# MP-USBC.net
KiCad netlist of a schematic drawn in Altium Designer
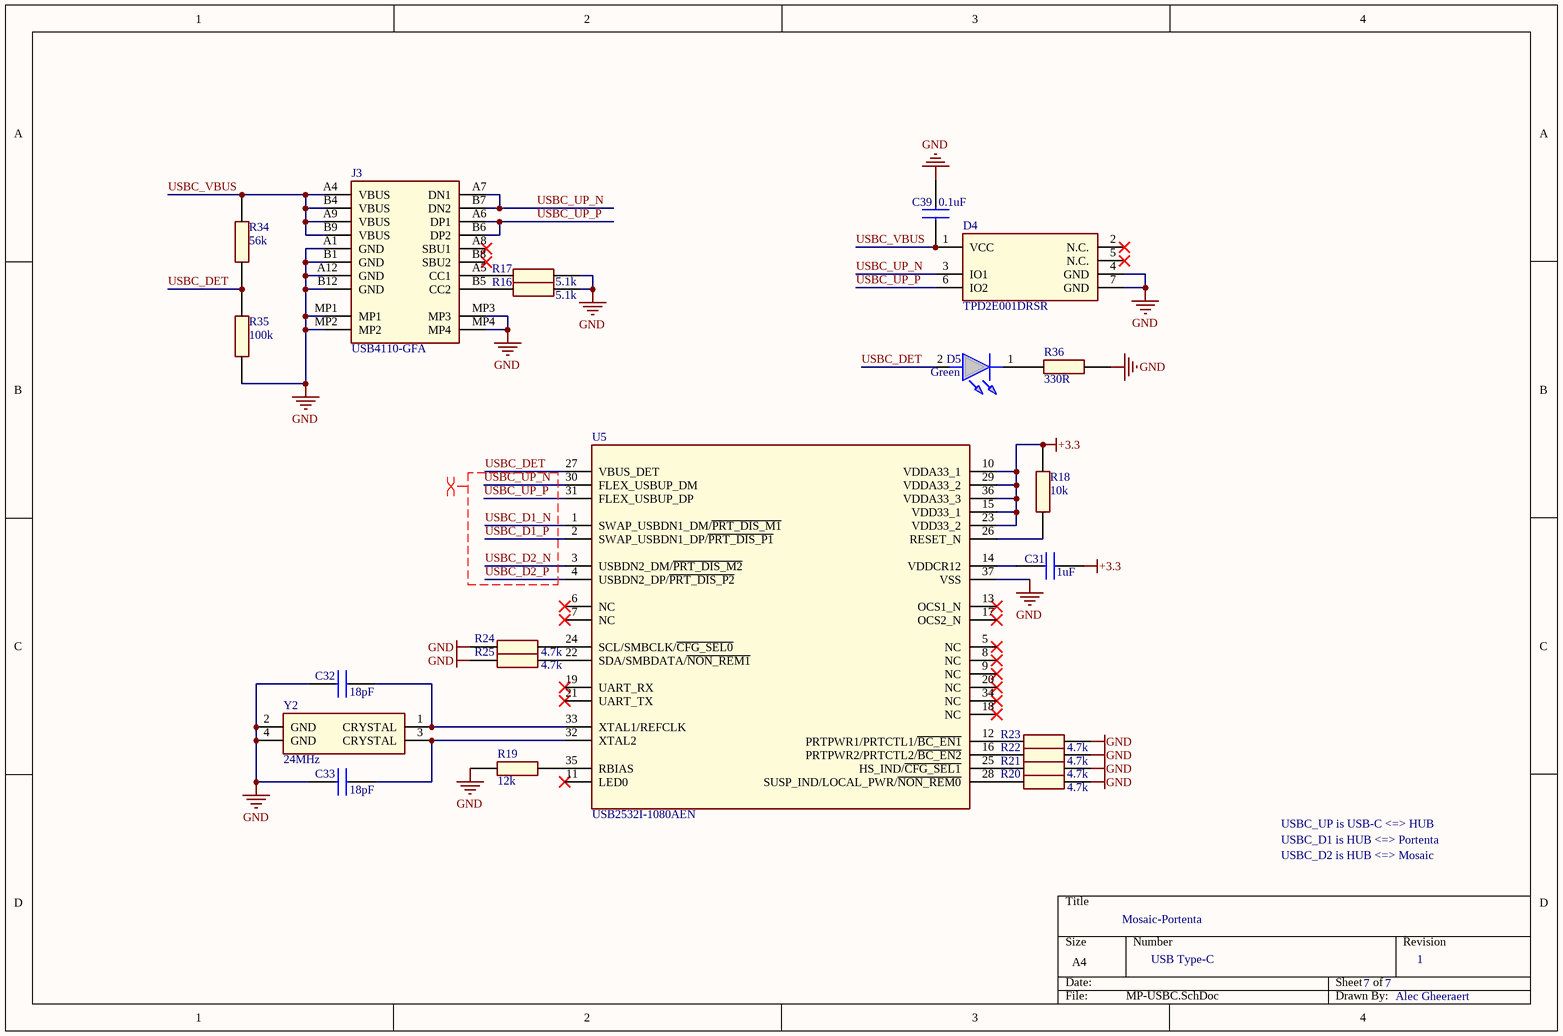
[diagram p0: MP-USBC.SchDoc]

(export (version "E")
  (design (tool "Eeschema 10.0.6"))
  (components
    (comp (ref "C31")
      (value "1uF")
      (footprint "CAPC1608X100N")
      (description "0603 1µF")
      (fields (field (name "MANUFACTURER") "Walsin") (field (name "TOLERANCE") "10%"))
      (libsource (lib "Ghrt") (part "0603X105K6R3CT"))
    )
    (comp (ref "C32")
      (value "18pF")
      (footprint "CAPC1608X87N")
      (description "0603 18pF")
      (fields (field (name "TOLERANCE") "5%") (field (name "MANUFACTURER") "Walsin"))
      (libsource (lib "Ghrt") (part "0603N180J160CT"))
    )
    (comp (ref "C33")
      (value "18pF")
      (footprint "CAPC1608X87N")
      (description "0603 18pF")
      (fields (field (name "TOLERANCE") "5%") (field (name "MANUFACTURER") "Walsin"))
      (libsource (lib "Ghrt") (part "0603N180J160CT"))
    )
    (comp (ref "C39")
      (value "0.1uF")
      (footprint "CAPC2012X145N")
      (description "0805I 0.1µF")
      (fields (field (name "MANUFACTURER") "Walsin") (field (name "TOLERANCE") "10%"))
      (libsource (lib "Ghrt") (part "MG21B104K101CT"))
    )
    (comp (ref "D4")
      (value "TPD2E001DRSR")
      (footprint "SON95P300X300X80-7N-D")
      (description "2-Channel TVS Diode")
      (libsource (lib "Ghrt") (part "TPD2E001DRSR"))
    )
    (comp (ref "D5")
      (value "Green")
      (footprint "APT1608ZGCAMT")
      (description "0603 Green LED")
      (libsource (lib "Ghrt") (part "APT1608ZGC-AMT"))
    )
    (comp (ref "J3")
      (value "USB4110-GFA")
      (footprint "USB4110-GFA")
      (description "USB-2.0 Type C")
      (fields (field (name "MANUFACTURER") "Global Connector Technologies"))
      (libsource (lib "Ghrt") (part "USB4110-GFA"))
    )
    (comp (ref "R16")
      (value "5.1k")
      (footprint "RESC1608X60N")
      (description "0603I 5.1k")
      (fields (field (name "MANUFACTURER") "Walsin") (field (name "TOLERANCE") "1%"))
      (libsource (lib "Ghrt") (part "WR06X5101FTL"))
    )
    (comp (ref "R17")
      (value "5.1k")
      (footprint "RESC1608X60N")
      (description "0603I 5.1k")
      (fields (field (name "MANUFACTURER") "Walsin") (field (name "TOLERANCE") "1%"))
      (libsource (lib "Ghrt") (part "WR06X5101FTL"))
    )
    (comp (ref "R18")
      (value "10k")
      (footprint "RESC1005X40N")
      (description "0402I 10k")
      (fields (field (name "MANUFACTURER") "Walsin") (field (name "TOLERANCE") "1%"))
      (libsource (lib "Ghrt") (part "WR04X1002FTL"))
    )
    (comp (ref "R19")
      (value "12k")
      (footprint "RESC1005X40N")
      (description "0402I 12k")
      (fields (field (name "TOLERANCE") "1%") (field (name "MANUFACTURER") "Walsin"))
      (libsource (lib "Ghrt") (part "WR04X1202FTL"))
    )
    (comp (ref "R20")
      (value "4.7k")
      (footprint "RESC1005X40N")
      (description "0402I 4.7k")
      (fields (field (name "MANUFACTURER") "Walsin") (field (name "TOLERANCE") "1%"))
      (libsource (lib "Ghrt") (part "WR04X4701FTL"))
    )
    (comp (ref "R21")
      (value "4.7k")
      (footprint "RESC1005X40N")
      (description "0402I 4.7k")
      (fields (field (name "MANUFACTURER") "Walsin") (field (name "TOLERANCE") "1%"))
      (libsource (lib "Ghrt") (part "WR04X4701FTL"))
    )
    (comp (ref "R22")
      (value "4.7k")
      (footprint "RESC1005X40N")
      (description "0402I 4.7k")
      (fields (field (name "MANUFACTURER") "Walsin") (field (name "TOLERANCE") "1%"))
      (libsource (lib "Ghrt") (part "WR04X4701FTL"))
    )
    (comp (ref "R23")
      (value "4.7k")
      (footprint "RESC1005X40N")
      (description "0402I 4.7k")
      (fields (field (name "MANUFACTURER") "Walsin") (field (name "TOLERANCE") "1%"))
      (libsource (lib "Ghrt") (part "WR04X4701FTL"))
    )
    (comp (ref "R24")
      (value "4.7k")
      (footprint "RESC1005X40N")
      (description "0402I 4.7k")
      (fields (field (name "MANUFACTURER") "Walsin") (field (name "TOLERANCE") "1%"))
      (libsource (lib "Ghrt") (part "WR04X4701FTL"))
    )
    (comp (ref "R25")
      (value "4.7k")
      (footprint "RESC1005X40N")
      (description "0402I 4.7k")
      (fields (field (name "MANUFACTURER") "Walsin") (field (name "TOLERANCE") "1%"))
      (libsource (lib "Ghrt") (part "WR04X4701FTL"))
    )
    (comp (ref "R34")
      (value "56k")
      (footprint "RESC1005X40N")
      (description "0402I 56k")
      (fields (field (name "TOLERANCE") "1%") (field (name "MANUFACTURER") "Walsin"))
      (libsource (lib "Ghrt") (part "WR04X5602FTL"))
    )
    (comp (ref "R35")
      (value "100k")
      (footprint "RESC1005X40N")
      (description "0402I 100k")
      (fields (field (name "MANUFACTURER") "Walsin") (field (name "TOLERANCE") "1%"))
      (libsource (lib "Ghrt") (part "WR04X1003FTL"))
    )
    (comp (ref "R36")
      (value "330R")
      (footprint "RESC1005X40N")
      (description "0402I 330")
      (fields (field (name "TOLERANCE") "1%") (field (name "MANUFACTURER") "Walsin"))
      (libsource (lib "Ghrt") (part "WR04X3300FTL"))
    )
    (comp (ref "U5")
      (value "USB2532I-1080AEN")
      (footprint "QFN50P600X600X100-37N-D")
      (description "2-Port USB-2.0 Controller Hub")
      (fields (field (name "MANUFACTURER") "Microchip"))
      (libsource (lib "Ghrt") (part "USB2532I-1080AEN"))
    )
    (comp (ref "Y2")
      (value "24MHz")
      (footprint "LFXTAL071257Reel")
      (description "24MHz +/-100ppm Crystal")
      (fields (field (name "TOLERANCE") "10") (field (name "MANUFACTURER") "IQD"))
      (libsource (lib "Ghrt") (part "LFXTAL071257Reel"))
    )
  )
  (nets
    (net (code "1") (name "+3.3") (class "Default")
      (node (ref "C31") (pin "2") (pinfunction "2_2") (pintype "passive"))
      (node (ref "R18") (pin "2") (pinfunction "2_2") (pintype "passive"))
      (node (ref "U5") (pin "10") (pinfunction "VDDA33_1_10") (pintype "passive"))
      (node (ref "U5") (pin "15") (pinfunction "VDD33_1_15") (pintype "passive"))
      (node (ref "U5") (pin "23") (pinfunction "VDD33_2_23") (pintype "passive"))
      (node (ref "U5") (pin "29") (pinfunction "VDDA33_2_29") (pintype "passive"))
      (node (ref "U5") (pin "36") (pinfunction "VDDA33_3_36") (pintype "passive"))
    )
    (net (code "3") (name "/USBC_D1_N") (class "Default")
      (node (ref "U5") (pin "1") (pinfunction "SWAP_USBDN1_DM/~{PRT_DIS_M1}_1") (pintype "passive"))
    )
    (net (code "4") (name "/USBC_D1_P") (class "Default")
      (node (ref "U5") (pin "2") (pinfunction "SWAP_USBDN1_DP/~{PRT_DIS_P1}_2") (pintype "passive"))
    )
    (net (code "5") (name "/USBC_D2_N") (class "Default")
      (node (ref "U5") (pin "3") (pinfunction "USBDN2_DM/~{PRT_DIS_M2}_3") (pintype "passive"))
    )
    (net (code "6") (name "/USBC_D2_P") (class "Default")
      (node (ref "U5") (pin "4") (pinfunction "USBDN2_DP/~{PRT_DIS_P2}_4") (pintype "passive"))
    )
    (net (code "7") (name "/USBC_DET") (class "Default")
      (node (ref "D5") (pin "2") (pinfunction "A_2") (pintype "passive"))
      (node (ref "R34") (pin "2") (pinfunction "2_2") (pintype "passive"))
      (node (ref "R35") (pin "1") (pinfunction "1_1") (pintype "passive"))
      (node (ref "U5") (pin "27") (pinfunction "VBUS_DET_27") (pintype "passive"))
    )
    (net (code "8") (name "/USBC_UP_N") (class "Default")
      (node (ref "D4") (pin "3") (pinfunction "IO1_3") (pintype "passive"))
      (node (ref "J3") (pin "A7") (pinfunction "DN1_A7") (pintype "passive"))
      (node (ref "J3") (pin "B7") (pinfunction "DN2_B7") (pintype "passive"))
      (node (ref "U5") (pin "30") (pinfunction "FLEX_USBUP_DM_30") (pintype "passive"))
    )
    (net (code "9") (name "/USBC_UP_P") (class "Default")
      (node (ref "D4") (pin "6") (pinfunction "IO2_6") (pintype "passive"))
      (node (ref "J3") (pin "A6") (pinfunction "DP1_A6") (pintype "passive"))
      (node (ref "J3") (pin "B6") (pinfunction "DP2_B6") (pintype "passive"))
      (node (ref "U5") (pin "31") (pinfunction "FLEX_USBUP_DP_31") (pintype "passive"))
    )
    (net (code "10") (name "/USBC_VBUS") (class "Default")
      (node (ref "C39") (pin "1") (pinfunction "1_1") (pintype "passive"))
      (node (ref "D4") (pin "1") (pinfunction "VCC_1") (pintype "passive"))
      (node (ref "J3") (pin "A4") (pinfunction "VBUS_A4") (pintype "passive"))
      (node (ref "J3") (pin "A9") (pinfunction "VBUS_A9") (pintype "passive"))
      (node (ref "J3") (pin "B4") (pinfunction "VBUS_B4") (pintype "passive"))
      (node (ref "J3") (pin "B9") (pinfunction "VBUS_B9") (pintype "passive"))
      (node (ref "R34") (pin "1") (pinfunction "1_1") (pintype "passive"))
    )
    (net (code "11") (name "GND") (class "Default")
      (node (ref "C32") (pin "1") (pinfunction "1_1") (pintype "passive"))
      (node (ref "C33") (pin "1") (pinfunction "1_1") (pintype "passive"))
      (node (ref "C39") (pin "2") (pinfunction "2_2") (pintype "passive"))
      (node (ref "D4") (pin "4") (pinfunction "GND_4") (pintype "passive"))
      (node (ref "D4") (pin "7") (pinfunction "GND_7") (pintype "passive"))
      (node (ref "J3") (pin "A1") (pinfunction "GND_A1") (pintype "passive"))
      (node (ref "J3") (pin "A12") (pinfunction "GND_A12") (pintype "passive"))
      (node (ref "J3") (pin "B1") (pinfunction "GND_B1") (pintype "passive"))
      (node (ref "J3") (pin "B12") (pinfunction "GND_B12") (pintype "passive"))
      (node (ref "J3") (pin "MP1") (pinfunction "MP1_MP1") (pintype "passive"))
      (node (ref "J3") (pin "MP2") (pinfunction "MP2_MP2") (pintype "passive"))
      (node (ref "J3") (pin "MP3") (pinfunction "MP3_MP3") (pintype "passive"))
      (node (ref "J3") (pin "MP4") (pinfunction "MP4_MP4") (pintype "passive"))
      (node (ref "R16") (pin "2") (pinfunction "2_2") (pintype "passive"))
      (node (ref "R17") (pin "2") (pinfunction "2_2") (pintype "passive"))
      (node (ref "R19") (pin "2") (pinfunction "2_2") (pintype "passive"))
      (node (ref "R20") (pin "2") (pinfunction "2_2") (pintype "passive"))
      (node (ref "R21") (pin "2") (pinfunction "2_2") (pintype "passive"))
      (node (ref "R22") (pin "2") (pinfunction "2_2") (pintype "passive"))
      (node (ref "R23") (pin "2") (pinfunction "2_2") (pintype "passive"))
      (node (ref "R24") (pin "1") (pinfunction "1_1") (pintype "passive"))
      (node (ref "R25") (pin "1") (pinfunction "1_1") (pintype "passive"))
      (node (ref "R35") (pin "2") (pinfunction "2_2") (pintype "passive"))
      (node (ref "R36") (pin "2") (pinfunction "2_2") (pintype "passive"))
      (node (ref "U5") (pin "37") (pinfunction "VSS_37") (pintype "passive"))
      (node (ref "Y2") (pin "2") (pinfunction "GND_2") (pintype "passive"))
      (node (ref "Y2") (pin "4") (pinfunction "GND_4") (pintype "passive"))
    )
    (net (code "12") (name "Net-(D5-K)") (class "Default")
      (node (ref "D5") (pin "1") (pinfunction "K_1") (pintype "passive"))
      (node (ref "R36") (pin "1") (pinfunction "1_1") (pintype "passive"))
    )
    (net (code "13") (name "Net-(J3-CC1)") (class "Default")
      (node (ref "J3") (pin "A5") (pinfunction "CC1_A5") (pintype "passive"))
      (node (ref "R17") (pin "1") (pinfunction "1_1") (pintype "passive"))
    )
    (net (code "14") (name "Net-(J3-CC2)") (class "Default")
      (node (ref "J3") (pin "B5") (pinfunction "CC2_B5") (pintype "passive"))
      (node (ref "R16") (pin "1") (pinfunction "1_1") (pintype "passive"))
    )
    (net (code "15") (name "Net-(U5-HS_IND{slash}~{CFG_SEL1})") (class "Default")
      (node (ref "R21") (pin "1") (pinfunction "1_1") (pintype "passive"))
      (node (ref "U5") (pin "25") (pinfunction "HS_IND/~{CFG_SEL1}_25") (pintype "passive"))
    )
    (net (code "16") (name "Net-(U5-PRTPWR1{slash}PRTCTL1{slash}~{BC_EN1})") (class "Default")
      (node (ref "R23") (pin "1") (pinfunction "1_1") (pintype "passive"))
      (node (ref "U5") (pin "12") (pinfunction "PRTPWR1/PRTCTL1/~{BC_EN1}_12") (pintype "passive"))
    )
    (net (code "17") (name "Net-(U5-PRTPWR2{slash}PRTCTL2{slash}~{BC_EN2})") (class "Default")
      (node (ref "R22") (pin "1") (pinfunction "1_1") (pintype "passive"))
      (node (ref "U5") (pin "16") (pinfunction "PRTPWR2/PRTCTL2/~{BC_EN2}_16") (pintype "passive"))
    )
    (net (code "18") (name "Net-(U5-RBIAS)") (class "Default")
      (node (ref "R19") (pin "1") (pinfunction "1_1") (pintype "passive"))
      (node (ref "U5") (pin "35") (pinfunction "RBIAS_35") (pintype "passive"))
    )
    (net (code "19") (name "Net-(U5-RESET_N)") (class "Default")
      (node (ref "R18") (pin "1") (pinfunction "1_1") (pintype "passive"))
      (node (ref "U5") (pin "26") (pinfunction "RESET_N_26") (pintype "passive"))
    )
    (net (code "20") (name "Net-(U5-SCL{slash}SMBCLK{slash}~{CFG_SEL0})") (class "Default")
      (node (ref "R24") (pin "2") (pinfunction "2_2") (pintype "passive"))
      (node (ref "U5") (pin "24") (pinfunction "SCL/SMBCLK/~{CFG_SEL0}_24") (pintype "passive"))
    )
    (net (code "21") (name "Net-(U5-SDA{slash}SMBDATA{slash}~{NON_REM1})") (class "Default")
      (node (ref "R25") (pin "2") (pinfunction "2_2") (pintype "passive"))
      (node (ref "U5") (pin "22") (pinfunction "SDA/SMBDATA/~{NON_REM1}_22") (pintype "passive"))
    )
    (net (code "22") (name "Net-(U5-SUSP_IND{slash}LOCAL_PWR{slash}~{NON_REM0})") (class "Default")
      (node (ref "R20") (pin "1") (pinfunction "1_1") (pintype "passive"))
      (node (ref "U5") (pin "28") (pinfunction "SUSP_IND/LOCAL_PWR/~{NON_REM0}_28") (pintype "passive"))
    )
    (net (code "23") (name "Net-(U5-VDDCR12)") (class "Default")
      (node (ref "C31") (pin "1") (pinfunction "1_1") (pintype "passive"))
      (node (ref "U5") (pin "14") (pinfunction "VDDCR12_14") (pintype "passive"))
    )
    (net (code "24") (name "Net-(U5-XTAL1{slash}REFCLK)") (class "Default")
      (node (ref "C32") (pin "2") (pinfunction "2_2") (pintype "passive"))
      (node (ref "U5") (pin "33") (pinfunction "XTAL1/REFCLK_33") (pintype "passive"))
      (node (ref "Y2") (pin "1") (pinfunction "CRYSTAL_1") (pintype "passive"))
    )
    (net (code "25") (name "Net-(U5-XTAL2)") (class "Default")
      (node (ref "C33") (pin "2") (pinfunction "2_2") (pintype "passive"))
      (node (ref "U5") (pin "32") (pinfunction "XTAL2_32") (pintype "passive"))
      (node (ref "Y2") (pin "3") (pinfunction "CRYSTAL_3") (pintype "passive"))
    )
    (net (code "26") (name "unconnected-(D4-N.C.-Pad2)") (class "Default")
      (node (ref "D4") (pin "2") (pinfunction "N.C._2") (pintype "passive+no_connect"))
    )
    (net (code "27") (name "unconnected-(D4-N.C.-Pad5)") (class "Default")
      (node (ref "D4") (pin "5") (pinfunction "N.C._5") (pintype "passive+no_connect"))
    )
    (net (code "28") (name "unconnected-(J3-SBU1-PadA8)") (class "Default")
      (node (ref "J3") (pin "A8") (pinfunction "SBU1_A8") (pintype "passive+no_connect"))
    )
    (net (code "29") (name "unconnected-(J3-SBU2-PadB8)") (class "Default")
      (node (ref "J3") (pin "B8") (pinfunction "SBU2_B8") (pintype "passive+no_connect"))
    )
    (net (code "30") (name "unconnected-(U5-LED0-Pad11)") (class "Default")
      (node (ref "U5") (pin "11") (pinfunction "LED0_11") (pintype "passive+no_connect"))
    )
    (net (code "31") (name "unconnected-(U5-NC-Pad5)") (class "Default")
      (node (ref "U5") (pin "5") (pinfunction "NC_5") (pintype "passive+no_connect"))
    )
    (net (code "32") (name "unconnected-(U5-NC-Pad6)") (class "Default")
      (node (ref "U5") (pin "6") (pinfunction "NC_6") (pintype "passive+no_connect"))
    )
    (net (code "33") (name "unconnected-(U5-NC-Pad7)") (class "Default")
      (node (ref "U5") (pin "7") (pinfunction "NC_7") (pintype "passive+no_connect"))
    )
    (net (code "34") (name "unconnected-(U5-NC-Pad8)") (class "Default")
      (node (ref "U5") (pin "8") (pinfunction "NC_8") (pintype "passive+no_connect"))
    )
    (net (code "35") (name "unconnected-(U5-NC-Pad9)") (class "Default")
      (node (ref "U5") (pin "9") (pinfunction "NC_9") (pintype "passive+no_connect"))
    )
    (net (code "36") (name "unconnected-(U5-NC-Pad18)") (class "Default")
      (node (ref "U5") (pin "18") (pinfunction "NC_18") (pintype "passive+no_connect"))
    )
    (net (code "37") (name "unconnected-(U5-NC-Pad20)") (class "Default")
      (node (ref "U5") (pin "20") (pinfunction "NC_20") (pintype "passive+no_connect"))
    )
    (net (code "38") (name "unconnected-(U5-NC-Pad34)") (class "Default")
      (node (ref "U5") (pin "34") (pinfunction "NC_34") (pintype "passive+no_connect"))
    )
    (net (code "39") (name "unconnected-(U5-OCS1_N-Pad13)") (class "Default")
      (node (ref "U5") (pin "13") (pinfunction "OCS1_N_13") (pintype "passive+no_connect"))
    )
    (net (code "40") (name "unconnected-(U5-OCS2_N-Pad17)") (class "Default")
      (node (ref "U5") (pin "17") (pinfunction "OCS2_N_17") (pintype "passive+no_connect"))
    )
    (net (code "41") (name "unconnected-(U5-UART_RX-Pad19)") (class "Default")
      (node (ref "U5") (pin "19") (pinfunction "UART_RX_19") (pintype "passive+no_connect"))
    )
    (net (code "42") (name "unconnected-(U5-UART_TX-Pad21)") (class "Default")
      (node (ref "U5") (pin "21") (pinfunction "UART_TX_21") (pintype "passive+no_connect"))
    )
  )
)
